# Ethernet.net
KiCad netlist of a schematic drawn in Altium Designer
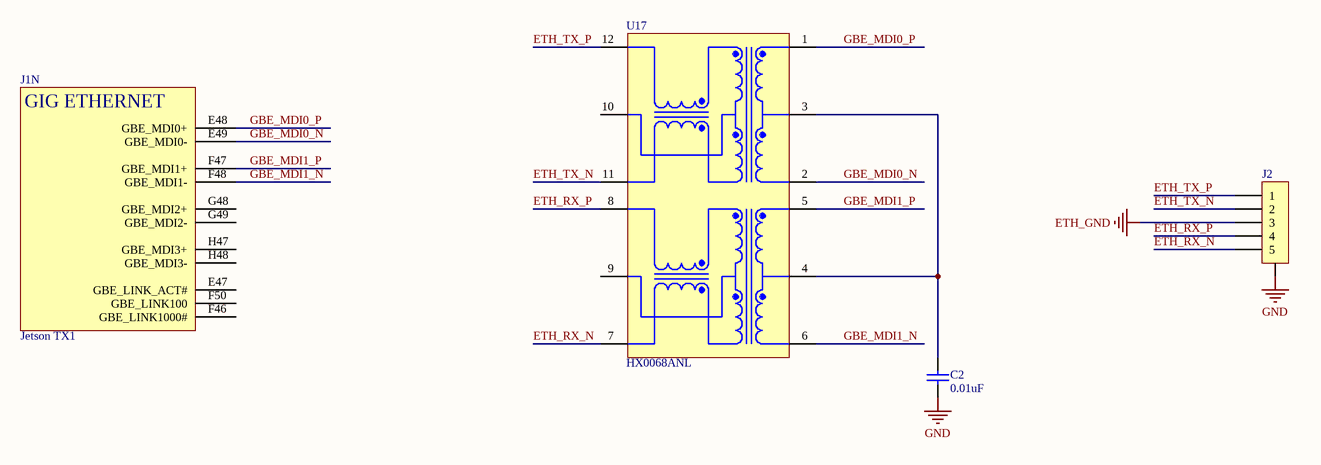
[diagram p0: Ethernet.SchDoc]

(export (version "E")
  (design (tool "Eeschema 10.0.6"))
  (components
    (comp (ref "C2")
      (value "0.01uF")
      (footprint "0402C_M")
      (description "CAP CER 0.01uF 50V X7R 0402")
      (fields
        (field (name "MANUFACTURER") "Murata Electronics North America")
        (field (name "MANUFACTURER PART NUMBER") "GRM155R71H103KA88D")
      )
      (libsource (lib "KMTI-main") (part "GRM155R71H103KA88D"))
    )
    (comp (ref "J1")
      (value "Jetson TX1")
      (footprint "Nvidia Jetson TX1")
      (description "Nvidia computing module")
      (libsource (lib "Modules") (part "NVIDIA_Jetson_TX1"))
    )
    (comp (ref "J2")
      (value "SM05B-GHS-TB(LF)(SN)")
      (footprint "SM05B-GHS-TB")
      (description "CONN HEADER GH SIDE 5POS 1.25MM")
      (fields (field (name "MANUFACTURER") "JST Sales America Inc."))
      (libsource (lib "KMTI-main") (part "SM05B-GHS-TB(LF)(SN)"))
    )
    (comp (ref "U17")
      (value "HX0068ANL")
      (footprint "PULS-HX0068ANL_V")
      (description "10 / 100 PC Card LAN Magnetic Module, -40 to 85 degC, 12-Pin SMD, RoHS, Tube")
      (fields (field (name "MANUFACTURER") "Pulse"))
      (libsource (lib "Altium Content Vault") (part "PULS-HX0068ANL-12"))
    )
  )
  (nets
    (net (code "1") (name "/ETH_RX_N") (class "Default")
      (node (ref "J2") (pin "5") (pinfunction "5_5") (pintype "passive"))
      (node (ref "U17") (pin "7") (pinfunction "TX-_7") (pintype "passive"))
    )
    (net (code "2") (name "/ETH_RX_P") (class "Default")
      (node (ref "J2") (pin "4") (pinfunction "4_4") (pintype "passive"))
      (node (ref "U17") (pin "8") (pinfunction "TX+_8") (pintype "passive"))
    )
    (net (code "3") (name "/ETH_TX_N") (class "Default")
      (node (ref "J2") (pin "2") (pinfunction "2_2") (pintype "passive"))
      (node (ref "U17") (pin "11") (pinfunction "RX-_11") (pintype "passive"))
    )
    (net (code "4") (name "/ETH_TX_P") (class "Default")
      (node (ref "J2") (pin "1") (pinfunction "1_1") (pintype "passive"))
      (node (ref "U17") (pin "12") (pinfunction "RX+_12") (pintype "passive"))
    )
    (net (code "5") (name "/GBE_MDI0_N") (class "Default")
      (node (ref "J1") (pin "E49") (pinfunction "GBE_MDI0-_E49") (pintype "passive"))
      (node (ref "U17") (pin "2") (pinfunction "RD-_2") (pintype "passive"))
    )
    (net (code "6") (name "/GBE_MDI0_P") (class "Default")
      (node (ref "J1") (pin "E48") (pinfunction "GBE_MDI0+_E48") (pintype "passive"))
      (node (ref "U17") (pin "1") (pinfunction "RD+_1") (pintype "passive"))
    )
    (net (code "7") (name "/GBE_MDI1_N") (class "Default")
      (node (ref "J1") (pin "F48") (pinfunction "GBE_MDI1-_F48") (pintype "passive"))
      (node (ref "U17") (pin "6") (pinfunction "TD-_6") (pintype "passive"))
    )
    (net (code "8") (name "/GBE_MDI1_P") (class "Default")
      (node (ref "J1") (pin "F47") (pinfunction "GBE_MDI1+_F47") (pintype "passive"))
      (node (ref "U17") (pin "5") (pinfunction "TD+_5") (pintype "passive"))
    )
    (net (code "9") (name "ETH_GND") (class "Default")
      (node (ref "J2") (pin "3") (pinfunction "3_3") (pintype "passive"))
    )
    (net (code "10") (name "GND") (class "Default")
      (node (ref "C2") (pin "1") (pinfunction "1_1") (pintype "passive"))
      (node (ref "J2") (pin "0") (pinfunction "0_0") (pintype "passive"))
    )
    (net (code "11") (name "Net-(U17-RDCT)") (class "Default")
      (node (ref "C2") (pin "2") (pinfunction "2_2") (pintype "passive"))
      (node (ref "U17") (pin "3") (pinfunction "RDCT_3") (pintype "passive"))
      (node (ref "U17") (pin "4") (pinfunction "TDCT_4") (pintype "passive"))
    )
    (net (code "12") (name "unconnected-(J1N-GBE_LINK100-PadF50)") (class "Default")
      (node (ref "J1") (pin "F50") (pinfunction "GBE_LINK100_F50") (pintype "passive"))
    )
    (net (code "13") (name "unconnected-(J1N-GBE_LINK1000#-PadF46)") (class "Default")
      (node (ref "J1") (pin "F46") (pinfunction "GBE_LINK1000#_F46") (pintype "passive"))
    )
    (net (code "14") (name "unconnected-(J1N-GBE_LINK_ACT#-PadE47)") (class "Default")
      (node (ref "J1") (pin "E47") (pinfunction "GBE_LINK_ACT#_E47") (pintype "passive"))
    )
    (net (code "15") (name "unconnected-(J1N-GBE_MDI2+-PadG48)") (class "Default")
      (node (ref "J1") (pin "G48") (pinfunction "GBE_MDI2+_G48") (pintype "passive"))
    )
    (net (code "16") (name "unconnected-(J1N-GBE_MDI2--PadG49)") (class "Default")
      (node (ref "J1") (pin "G49") (pinfunction "GBE_MDI2-_G49") (pintype "passive"))
    )
    (net (code "17") (name "unconnected-(J1N-GBE_MDI3+-PadH47)") (class "Default")
      (node (ref "J1") (pin "H47") (pinfunction "GBE_MDI3+_H47") (pintype "passive"))
    )
    (net (code "18") (name "unconnected-(J1N-GBE_MDI3--PadH48)") (class "Default")
      (node (ref "J1") (pin "H48") (pinfunction "GBE_MDI3-_H48") (pintype "passive"))
    )
    (net (code "19") (name "unconnected-(U17-RXCT-Pad10)") (class "Default")
      (node (ref "U17") (pin "10") (pinfunction "RXCT_10") (pintype "passive"))
    )
    (net (code "20") (name "unconnected-(U17-TXCT-Pad9)") (class "Default")
      (node (ref "U17") (pin "9") (pinfunction "TXCT_9") (pintype "passive"))
    )
  )
)
